# HLK-W806-KIT-V1_0.net
KiCad netlist of a schematic drawn in Altium Designer
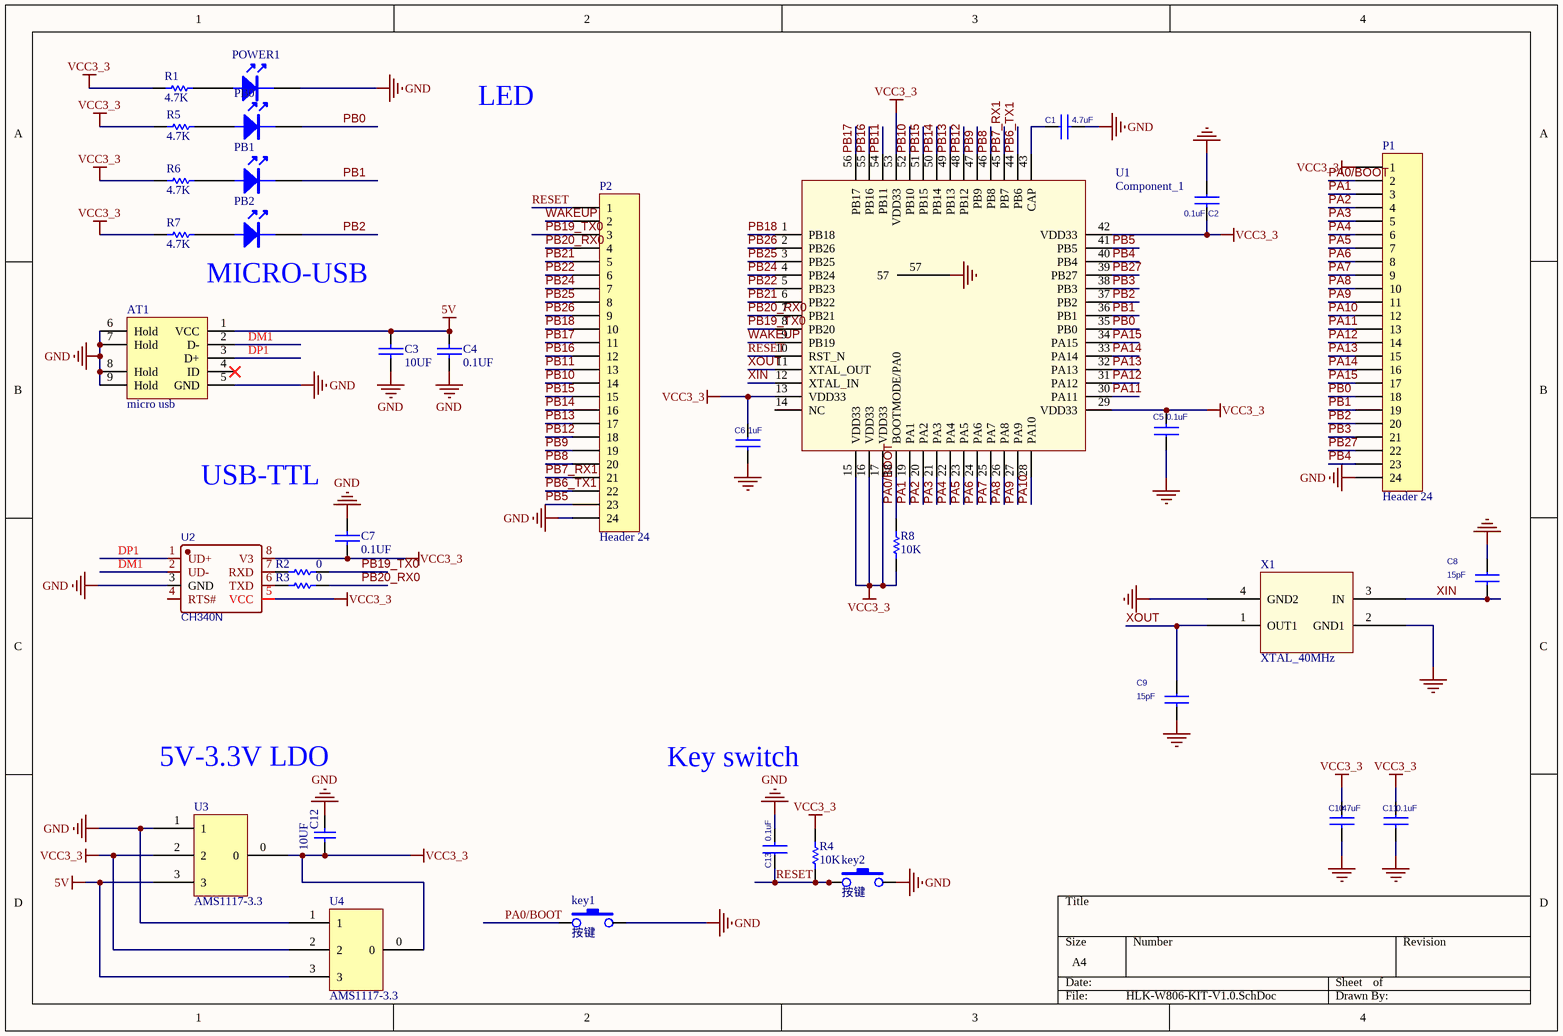
[diagram p0: HLK-W806-KIT-V1.0.SchDoc]

(export (version "E")
  (design (tool "Eeschema 10.0.6"))
  (components
    (comp (ref "AT1")
      (value "micro usb")
      (footprint "USB-MICRO_D")
      (libsource (lib "HLK-N10-KIT-V1.0") (part "USB-D"))
    )
    (comp (ref "C1") (value "4.7uF") (footprint "0603") (libsource (lib "*") (part "CAP NP_Dup1")))
    (comp (ref "C2") (value "0.1uF") (footprint "0603") (libsource (lib "*") (part "CAP NP_Dup1")))
    (comp (ref "C3")
      (value "10UF")
      (footprint "0603_1")
      (description "Capacitor")
      (libsource (lib "*") (part "CAP"))
    )
    (comp (ref "C4")
      (value "0.1UF")
      (footprint "0603_1")
      (description "Capacitor")
      (libsource (lib "*") (part "CAP"))
    )
    (comp (ref "C5") (value "0.1uF") (footprint "0603") (libsource (lib "*") (part "CAP NP_Dup1")))
    (comp (ref "C6") (value "1uF") (footprint "0603") (libsource (lib "*") (part "CAP NP_Dup1")))
    (comp (ref "C7")
      (value "0.1UF")
      (footprint "0603_1")
      (description "Capacitor")
      (libsource (lib "*") (part "CAP"))
    )
    (comp (ref "C8") (value "15pF") (footprint "0603") (libsource (lib "*") (part "CAP NP_Dup1")))
    (comp (ref "C9") (value "15pF") (footprint "0603") (libsource (lib "*") (part "CAP NP_Dup1")))
    (comp (ref "C10") (value "47uF") (footprint "R0805") (libsource (lib "*") (part "CAP NP_Dup1")))
    (comp (ref "C11") (value "0.1uF") (footprint "0603") (libsource (lib "*") (part "CAP NP_Dup1")))
    (comp (ref "C12")
      (value "10UF")
      (footprint "0603_1")
      (description "Capacitor")
      (fields (field (name "PUBLISHER") "Altium Limited"))
      (libsource (lib "Miscellaneous Devices") (part "Cap"))
    )
    (comp (ref "C13") (value "0.1uF") (footprint "0603") (libsource (lib "*") (part "CAP NP_Dup1")))
    (comp (ref "key1") (value "按键") (footprint "正按小龟") (libsource (lib "标准通用原理图库") (part "按键")))
    (comp (ref "key2") (value "按键") (footprint "正按小龟") (libsource (lib "标准通用原理图库") (part "按键")))
    (comp (ref "P1")
      (value "Header 24")
      (footprint "HDR1X24")
      (description "Header, 24-Pin")
      (fields (field (name "PUBLISHER") "Altium Limited"))
      (libsource (lib "Miscellaneous Connectors") (part "Header 24"))
    )
    (comp (ref "P2")
      (value "Header 24")
      (footprint "HDR1X24")
      (description "Header, 24-Pin")
      (fields (field (name "PUBLISHER") "Altium Limited"))
      (libsource (lib "Miscellaneous Connectors") (part "Header 24"))
    )
    (comp (ref "PB0")
      (value "~")
      (footprint "0603LED")
      (libsource (lib "Miscellaneous Devices") (part "LED"))
    )
    (comp (ref "PB1")
      (value "~")
      (footprint "0603LED")
      (libsource (lib "Miscellaneous Devices") (part "LED"))
    )
    (comp (ref "PB2")
      (value "~")
      (footprint "0603LED")
      (libsource (lib "Miscellaneous Devices") (part "LED"))
    )
    (comp (ref "POWER1")
      (value "~")
      (footprint "0603LED")
      (libsource (lib "Miscellaneous Devices") (part "LED"))
    )
    (comp (ref "R1")
      (value "4.7K")
      (footprint "0603_1")
      (description "Resistor")
      (fields (field (name "PUBLISHER") "Altium Limited"))
      (libsource (lib "Miscellaneous Devices") (part "Res1"))
    )
    (comp (ref "R2")
      (value "0")
      (footprint "0603_1")
      (description "Resistor")
      (fields (field (name "PUBLISHER") "Altium Limited"))
      (libsource (lib "Miscellaneous Devices") (part "Res1"))
    )
    (comp (ref "R3")
      (value "0")
      (footprint "0603_1")
      (description "Resistor")
      (fields (field (name "PUBLISHER") "Altium Limited"))
      (libsource (lib "Miscellaneous Devices") (part "Res1"))
    )
    (comp (ref "R4")
      (value "10K")
      (footprint "0603_1")
      (description "Resistor")
      (fields (field (name "PUBLISHER") "Altium Limited"))
      (libsource (lib "Miscellaneous Devices") (part "Res1"))
    )
    (comp (ref "R5")
      (value "4.7K")
      (footprint "0603_1")
      (description "Resistor")
      (fields (field (name "PUBLISHER") "Altium Limited"))
      (libsource (lib "Miscellaneous Devices") (part "Res1"))
    )
    (comp (ref "R6")
      (value "4.7K")
      (footprint "0603_1")
      (description "Resistor")
      (fields (field (name "PUBLISHER") "Altium Limited"))
      (libsource (lib "Miscellaneous Devices") (part "Res1"))
    )
    (comp (ref "R7")
      (value "4.7K")
      (footprint "0603_1")
      (description "Resistor")
      (fields (field (name "PUBLISHER") "Altium Limited"))
      (libsource (lib "Miscellaneous Devices") (part "Res1"))
    )
    (comp (ref "R8")
      (value "10K")
      (footprint "0603_1")
      (description "Resistor")
      (fields (field (name "PUBLISHER") "Altium Limited"))
      (libsource (lib "Miscellaneous Devices") (part "Res1"))
    )
    (comp (ref "U1")
      (value "Component_1")
      (footprint "LCC56 - duplicate1")
      (libsource (lib "Schlib") (part "Component_1"))
    )
    (comp (ref "U2")
      (value "CH340N")
      (footprint "SOP8")
      (fields (field (name "BOM_SUPPLIER PART") "C506813") (field (name "CONTRIBUTOR") "LCSC"))
      (libsource (lib "Schlib1") (part "CH340N"))
    )
    (comp (ref "U3")
      (value "AMS1117-3.3")
      (footprint "AMS1117")
      (libsource (lib "Schlib1") (part "Component_1"))
    )
    (comp (ref "U4")
      (value "AMS1117-3.3")
      (footprint "SOT223")
      (libsource (lib "Schlib1") (part "Component_1"))
    )
    (comp (ref "X1")
      (value "XTAL_40MHz")
      (footprint "SMD-3225")
      (libsource (lib "Schlib1") (part "XTAL_40MHz"))
    )
  )
  (nets
    (net (code "1") (name "/DM1") (class "Default")
      (node (ref "AT1") (pin "2") (pinfunction "D-_2") (pintype "passive"))
      (node (ref "U2") (pin "2") (pinfunction "UD-_2") (pintype "passive"))
    )
    (net (code "2") (name "/DP1") (class "Default")
      (node (ref "AT1") (pin "3") (pinfunction "D+_3") (pintype "passive"))
      (node (ref "U2") (pin "1") (pinfunction "UD+_1") (pintype "passive"))
    )
    (net (code "3") (name "/PA0{slash}BOOT") (class "Default")
      (node (ref "P1") (pin "2") (pinfunction "2_2") (pintype "passive"))
      (node (ref "R8") (pin "2") (pinfunction "2_2") (pintype "passive"))
      (node (ref "U1") (pin "18") (pinfunction "BOOTMODE/PA0_18") (pintype "passive"))
      (node (ref "key1") (pin "1") (pinfunction "1_1") (pintype "passive"))
    )
    (net (code "4") (name "/PA1") (class "Default")
      (node (ref "P1") (pin "3") (pinfunction "3_3") (pintype "passive"))
      (node (ref "U1") (pin "19") (pinfunction "PA1_19") (pintype "passive"))
    )
    (net (code "5") (name "/PA2") (class "Default")
      (node (ref "P1") (pin "4") (pinfunction "4_4") (pintype "passive"))
      (node (ref "U1") (pin "20") (pinfunction "PA2_20") (pintype "passive"))
    )
    (net (code "6") (name "/PA3") (class "Default")
      (node (ref "P1") (pin "5") (pinfunction "5_5") (pintype "passive"))
      (node (ref "U1") (pin "21") (pinfunction "PA3_21") (pintype "passive"))
    )
    (net (code "7") (name "/PA4") (class "Default")
      (node (ref "P1") (pin "6") (pinfunction "6_6") (pintype "passive"))
      (node (ref "U1") (pin "22") (pinfunction "PA4_22") (pintype "passive"))
    )
    (net (code "8") (name "/PA5") (class "Default")
      (node (ref "P1") (pin "7") (pinfunction "7_7") (pintype "passive"))
      (node (ref "U1") (pin "23") (pinfunction "PA5_23") (pintype "passive"))
    )
    (net (code "9") (name "/PA6") (class "Default")
      (node (ref "P1") (pin "8") (pinfunction "8_8") (pintype "passive"))
      (node (ref "U1") (pin "24") (pinfunction "PA6_24") (pintype "passive"))
    )
    (net (code "10") (name "/PA7") (class "Default")
      (node (ref "P1") (pin "9") (pinfunction "9_9") (pintype "passive"))
      (node (ref "U1") (pin "25") (pinfunction "PA7_25") (pintype "passive"))
    )
    (net (code "11") (name "/PA8") (class "Default")
      (node (ref "P1") (pin "10") (pinfunction "10_10") (pintype "passive"))
      (node (ref "U1") (pin "26") (pinfunction "PA8_26") (pintype "passive"))
    )
    (net (code "12") (name "/PA9") (class "Default")
      (node (ref "P1") (pin "11") (pinfunction "11_11") (pintype "passive"))
      (node (ref "U1") (pin "27") (pinfunction "PA9_27") (pintype "passive"))
    )
    (net (code "13") (name "/PA10") (class "Default")
      (node (ref "P1") (pin "12") (pinfunction "12_12") (pintype "passive"))
      (node (ref "U1") (pin "28") (pinfunction "PA10_28") (pintype "passive"))
    )
    (net (code "14") (name "/PA11") (class "Default")
      (node (ref "P1") (pin "13") (pinfunction "13_13") (pintype "passive"))
      (node (ref "U1") (pin "30") (pinfunction "PA11_30") (pintype "passive"))
    )
    (net (code "15") (name "/PA12") (class "Default")
      (node (ref "P1") (pin "14") (pinfunction "14_14") (pintype "passive"))
      (node (ref "U1") (pin "31") (pinfunction "PA12_31") (pintype "passive"))
    )
    (net (code "16") (name "/PA13") (class "Default")
      (node (ref "P1") (pin "15") (pinfunction "15_15") (pintype "passive"))
      (node (ref "U1") (pin "32") (pinfunction "PA13_32") (pintype "passive"))
    )
    (net (code "17") (name "/PA14") (class "Default")
      (node (ref "P1") (pin "16") (pinfunction "16_16") (pintype "passive"))
      (node (ref "U1") (pin "33") (pinfunction "PA14_33") (pintype "passive"))
    )
    (net (code "18") (name "/PA15") (class "Default")
      (node (ref "P1") (pin "17") (pinfunction "17_17") (pintype "passive"))
      (node (ref "U1") (pin "34") (pinfunction "PA15_34") (pintype "passive"))
    )
    (net (code "19") (name "/PB0") (class "Default")
      (node (ref "P1") (pin "18") (pinfunction "18_18") (pintype "passive"))
      (node (ref "PB0") (pin "2") (pinfunction "2_2") (pintype "passive"))
      (node (ref "U1") (pin "35") (pinfunction "PB0_35") (pintype "passive"))
    )
    (net (code "20") (name "/PB1") (class "Default")
      (node (ref "P1") (pin "19") (pinfunction "19_19") (pintype "passive"))
      (node (ref "PB1") (pin "2") (pinfunction "2_2") (pintype "passive"))
      (node (ref "U1") (pin "36") (pinfunction "PB1_36") (pintype "passive"))
    )
    (net (code "21") (name "/PB2") (class "Default")
      (node (ref "P1") (pin "20") (pinfunction "20_20") (pintype "passive"))
      (node (ref "PB2") (pin "2") (pinfunction "2_2") (pintype "passive"))
      (node (ref "U1") (pin "37") (pinfunction "PB2_37") (pintype "passive"))
    )
    (net (code "22") (name "/PB3") (class "Default")
      (node (ref "P1") (pin "21") (pinfunction "21_21") (pintype "passive"))
      (node (ref "U1") (pin "38") (pinfunction "PB3_38") (pintype "passive"))
    )
    (net (code "23") (name "/PB4") (class "Default")
      (node (ref "P1") (pin "23") (pinfunction "23_23") (pintype "passive"))
      (node (ref "U1") (pin "40") (pinfunction "PB4_40") (pintype "passive"))
    )
    (net (code "24") (name "/PB5") (class "Default")
      (node (ref "P2") (pin "23") (pinfunction "23_23") (pintype "passive"))
      (node (ref "U1") (pin "41") (pinfunction "PB5_41") (pintype "passive"))
    )
    (net (code "25") (name "/PB6_TX1") (class "Default")
      (node (ref "P2") (pin "22") (pinfunction "22_22") (pintype "passive"))
      (node (ref "U1") (pin "44") (pinfunction "PB6_44") (pintype "passive"))
    )
    (net (code "26") (name "/PB7_RX1") (class "Default")
      (node (ref "P2") (pin "21") (pinfunction "21_21") (pintype "passive"))
      (node (ref "U1") (pin "45") (pinfunction "PB7_45") (pintype "passive"))
    )
    (net (code "27") (name "/PB8") (class "Default")
      (node (ref "P2") (pin "20") (pinfunction "20_20") (pintype "passive"))
      (node (ref "U1") (pin "46") (pinfunction "PB8_46") (pintype "passive"))
    )
    (net (code "28") (name "/PB9") (class "Default")
      (node (ref "P2") (pin "19") (pinfunction "19_19") (pintype "passive"))
      (node (ref "U1") (pin "47") (pinfunction "PB9_47") (pintype "passive"))
    )
    (net (code "29") (name "/PB10") (class "Default")
      (node (ref "P2") (pin "14") (pinfunction "14_14") (pintype "passive"))
      (node (ref "U1") (pin "52") (pinfunction "PB10_52") (pintype "passive"))
    )
    (net (code "30") (name "/PB11") (class "Default")
      (node (ref "P2") (pin "13") (pinfunction "13_13") (pintype "passive"))
      (node (ref "U1") (pin "54") (pinfunction "PB11_54") (pintype "passive"))
    )
    (net (code "31") (name "/PB12") (class "Default")
      (node (ref "P2") (pin "18") (pinfunction "18_18") (pintype "passive"))
      (node (ref "U1") (pin "48") (pinfunction "PB12_48") (pintype "passive"))
    )
    (net (code "32") (name "/PB13") (class "Default")
      (node (ref "P2") (pin "17") (pinfunction "17_17") (pintype "passive"))
      (node (ref "U1") (pin "49") (pinfunction "PB13_49") (pintype "passive"))
    )
    (net (code "33") (name "/PB14") (class "Default")
      (node (ref "P2") (pin "16") (pinfunction "16_16") (pintype "passive"))
      (node (ref "U1") (pin "50") (pinfunction "PB14_50") (pintype "passive"))
    )
    (net (code "34") (name "/PB15") (class "Default")
      (node (ref "P2") (pin "15") (pinfunction "15_15") (pintype "passive"))
      (node (ref "U1") (pin "51") (pinfunction "PB15_51") (pintype "passive"))
    )
    (net (code "35") (name "/PB16") (class "Default")
      (node (ref "P2") (pin "12") (pinfunction "12_12") (pintype "passive"))
      (node (ref "U1") (pin "55") (pinfunction "PB16_55") (pintype "passive"))
    )
    (net (code "36") (name "/PB17") (class "Default")
      (node (ref "P2") (pin "11") (pinfunction "11_11") (pintype "passive"))
      (node (ref "U1") (pin "56") (pinfunction "PB17_56") (pintype "passive"))
    )
    (net (code "37") (name "/PB18") (class "Default")
      (node (ref "P2") (pin "10") (pinfunction "10_10") (pintype "passive"))
      (node (ref "U1") (pin "1") (pinfunction "PB18_1") (pintype "passive"))
    )
    (net (code "38") (name "/PB19_TX0") (class "Default")
      (node (ref "P2") (pin "3") (pinfunction "3_3") (pintype "passive"))
      (node (ref "R2") (pin "2") (pinfunction "2_2") (pintype "passive"))
      (node (ref "U1") (pin "8") (pinfunction "PB20_8") (pintype "passive"))
    )
    (net (code "39") (name "/PB20_RX0") (class "Default")
      (node (ref "P2") (pin "4") (pinfunction "4_4") (pintype "passive"))
      (node (ref "R3") (pin "2") (pinfunction "2_2") (pintype "passive"))
      (node (ref "U1") (pin "7") (pinfunction "PB21_7") (pintype "passive"))
    )
    (net (code "40") (name "/PB21") (class "Default")
      (node (ref "P2") (pin "5") (pinfunction "5_5") (pintype "passive"))
      (node (ref "U1") (pin "6") (pinfunction "PB22_6") (pintype "passive"))
    )
    (net (code "41") (name "/PB22") (class "Default")
      (node (ref "P2") (pin "6") (pinfunction "6_6") (pintype "passive"))
      (node (ref "U1") (pin "5") (pinfunction "PB23_5") (pintype "passive"))
    )
    (net (code "42") (name "/PB24") (class "Default")
      (node (ref "P2") (pin "7") (pinfunction "7_7") (pintype "passive"))
      (node (ref "U1") (pin "4") (pinfunction "PB24_4") (pintype "passive"))
    )
    (net (code "43") (name "/PB25") (class "Default")
      (node (ref "P2") (pin "8") (pinfunction "8_8") (pintype "passive"))
      (node (ref "U1") (pin "3") (pinfunction "PB25_3") (pintype "passive"))
    )
    (net (code "44") (name "/PB26") (class "Default")
      (node (ref "P2") (pin "9") (pinfunction "9_9") (pintype "passive"))
      (node (ref "U1") (pin "2") (pinfunction "PB26_2") (pintype "passive"))
    )
    (net (code "45") (name "/PB27") (class "Default")
      (node (ref "P1") (pin "22") (pinfunction "22_22") (pintype "passive"))
      (node (ref "U1") (pin "39") (pinfunction "PB27_39") (pintype "passive"))
    )
    (net (code "46") (name "/RESET") (class "Default")
      (node (ref "C13") (pin "1") (pinfunction "1_1") (pintype "passive"))
      (node (ref "P2") (pin "1") (pinfunction "1_1") (pintype "passive"))
      (node (ref "R4") (pin "1") (pinfunction "1_1") (pintype "passive"))
      (node (ref "U1") (pin "10") (pinfunction "RST_N_10") (pintype "passive"))
      (node (ref "key2") (pin "1") (pinfunction "1_1") (pintype "passive"))
    )
    (net (code "47") (name "/WAKEUP") (class "Default")
      (node (ref "P2") (pin "2") (pinfunction "2_2") (pintype "passive"))
      (node (ref "U1") (pin "9") (pinfunction "PB19_9") (pintype "passive"))
    )
    (net (code "48") (name "/XIN") (class "Default")
      (node (ref "C8") (pin "2") (pinfunction "2_2") (pintype "passive"))
      (node (ref "U1") (pin "12") (pinfunction "XTAL_IN_12") (pintype "passive"))
      (node (ref "X1") (pin "3") (pinfunction "IN_3") (pintype "passive"))
    )
    (net (code "49") (name "/XOUT") (class "Default")
      (node (ref "C9") (pin "1") (pinfunction "1_1") (pintype "passive"))
      (node (ref "U1") (pin "11") (pinfunction "XTAL_OUT_11") (pintype "passive"))
      (node (ref "X1") (pin "1") (pinfunction "OUT1_1") (pintype "passive"))
    )
    (net (code "50") (name "5V") (class "Default")
      (node (ref "AT1") (pin "1") (pinfunction "VCC_1") (pintype "passive"))
      (node (ref "C3") (pin "2") (pinfunction "2_2") (pintype "passive"))
      (node (ref "C4") (pin "2") (pinfunction "2_2") (pintype "passive"))
      (node (ref "U3") (pin "3") (pinfunction "3_3") (pintype "passive"))
      (node (ref "U4") (pin "3") (pinfunction "3_3") (pintype "passive"))
    )
    (net (code "51") (name "GND") (class "Default")
      (node (ref "AT1") (pin "5") (pinfunction "GND_5") (pintype "passive"))
      (node (ref "AT1") (pin "6") (pinfunction "Hold_6") (pintype "passive"))
      (node (ref "AT1") (pin "7") (pinfunction "Hold_7") (pintype "passive"))
      (node (ref "AT1") (pin "8") (pinfunction "Hold_8") (pintype "passive"))
      (node (ref "AT1") (pin "9") (pinfunction "Hold_9") (pintype "passive"))
      (node (ref "C1") (pin "2") (pinfunction "2_2") (pintype "passive"))
      (node (ref "C10") (pin "2") (pinfunction "2_2") (pintype "passive"))
      (node (ref "C11") (pin "2") (pinfunction "2_2") (pintype "passive"))
      (node (ref "C12") (pin "1") (pinfunction "1_1") (pintype "passive"))
      (node (ref "C13") (pin "2") (pinfunction "2_2") (pintype "passive"))
      (node (ref "C2") (pin "1") (pinfunction "1_1") (pintype "passive"))
      (node (ref "C3") (pin "1") (pinfunction "1_1") (pintype "passive"))
      (node (ref "C4") (pin "1") (pinfunction "1_1") (pintype "passive"))
      (node (ref "C5") (pin "1") (pinfunction "1_1") (pintype "passive"))
      (node (ref "C6") (pin "2") (pinfunction "2_2") (pintype "passive"))
      (node (ref "C7") (pin "1") (pinfunction "1_1") (pintype "passive"))
      (node (ref "C8") (pin "1") (pinfunction "1_1") (pintype "passive"))
      (node (ref "C9") (pin "2") (pinfunction "2_2") (pintype "passive"))
      (node (ref "P1") (pin "24") (pinfunction "24_24") (pintype "passive"))
      (node (ref "P2") (pin "24") (pinfunction "24_24") (pintype "passive"))
      (node (ref "POWER1") (pin "2") (pinfunction "2_2") (pintype "passive"))
      (node (ref "U1") (pin "57") (pinfunction "57_57") (pintype "passive"))
      (node (ref "U2") (pin "3") (pinfunction "GND_3") (pintype "passive"))
      (node (ref "U3") (pin "1") (pinfunction "1_1") (pintype "passive"))
      (node (ref "U4") (pin "1") (pinfunction "1_1") (pintype "passive"))
      (node (ref "X1") (pin "2") (pinfunction "GND1_2") (pintype "passive"))
      (node (ref "X1") (pin "4") (pinfunction "GND2_4") (pintype "passive"))
      (node (ref "key1") (pin "2") (pinfunction "2_2") (pintype "passive"))
      (node (ref "key2") (pin "2") (pinfunction "2_2") (pintype "passive"))
    )
    (net (code "52") (name "Net-(PB0-Pad1)") (class "Default")
      (node (ref "PB0") (pin "1") (pinfunction "1_1") (pintype "passive"))
      (node (ref "R5") (pin "2") (pinfunction "2_2") (pintype "passive"))
    )
    (net (code "53") (name "Net-(PB1-Pad1)") (class "Default")
      (node (ref "PB1") (pin "1") (pinfunction "1_1") (pintype "passive"))
      (node (ref "R6") (pin "2") (pinfunction "2_2") (pintype "passive"))
    )
    (net (code "54") (name "Net-(PB2-Pad1)") (class "Default")
      (node (ref "PB2") (pin "1") (pinfunction "1_1") (pintype "passive"))
      (node (ref "R7") (pin "2") (pinfunction "2_2") (pintype "passive"))
    )
    (net (code "55") (name "Net-(POWER1-Pad1)") (class "Default")
      (node (ref "POWER1") (pin "1") (pinfunction "1_1") (pintype "passive"))
      (node (ref "R1") (pin "2") (pinfunction "2_2") (pintype "passive"))
    )
    (net (code "56") (name "Net-(U1-CAP)") (class "Default")
      (node (ref "C1") (pin "1") (pinfunction "1_1") (pintype "passive"))
      (node (ref "U1") (pin "43") (pinfunction "CAP_43") (pintype "passive"))
    )
    (net (code "57") (name "Net-(U2-RXD)") (class "Default")
      (node (ref "R2") (pin "1") (pinfunction "1_1") (pintype "passive"))
      (node (ref "U2") (pin "7") (pinfunction "RXD_7") (pintype "passive"))
    )
    (net (code "58") (name "Net-(U2-TXD)") (class "Default")
      (node (ref "R3") (pin "1") (pinfunction "1_1") (pintype "passive"))
      (node (ref "U2") (pin "6") (pinfunction "TXD_6") (pintype "passive"))
    )
    (net (code "59") (name "VCC3_3") (class "Default")
      (node (ref "C10") (pin "1") (pinfunction "1_1") (pintype "passive"))
      (node (ref "C11") (pin "1") (pinfunction "1_1") (pintype "passive"))
      (node (ref "C12") (pin "2") (pinfunction "2_2") (pintype "passive"))
      (node (ref "C2") (pin "2") (pinfunction "2_2") (pintype "passive"))
      (node (ref "C5") (pin "2") (pinfunction "2_2") (pintype "passive"))
      (node (ref "C6") (pin "1") (pinfunction "1_1") (pintype "passive"))
      (node (ref "C7") (pin "2") (pinfunction "2_2") (pintype "passive"))
      (node (ref "P1") (pin "1") (pinfunction "1_1") (pintype "passive"))
      (node (ref "R1") (pin "1") (pinfunction "1_1") (pintype "passive"))
      (node (ref "R4") (pin "2") (pinfunction "2_2") (pintype "passive"))
      (node (ref "R5") (pin "1") (pinfunction "1_1") (pintype "passive"))
      (node (ref "R6") (pin "1") (pinfunction "1_1") (pintype "passive"))
      (node (ref "R7") (pin "1") (pinfunction "1_1") (pintype "passive"))
      (node (ref "R8") (pin "1") (pinfunction "1_1") (pintype "passive"))
      (node (ref "U1") (pin "13") (pinfunction "VDD33_13") (pintype "passive"))
      (node (ref "U1") (pin "15") (pinfunction "VDD33_15") (pintype "passive"))
      (node (ref "U1") (pin "16") (pinfunction "VDD33_16") (pintype "passive"))
      (node (ref "U1") (pin "17") (pinfunction "VDD33_17") (pintype "passive"))
      (node (ref "U1") (pin "29") (pinfunction "VDD33_29") (pintype "passive"))
      (node (ref "U1") (pin "42") (pinfunction "VDD33_42") (pintype "passive"))
      (node (ref "U1") (pin "53") (pinfunction "VDD33_53") (pintype "passive"))
      (node (ref "U2") (pin "5") (pinfunction "VCC_5") (pintype "passive"))
      (node (ref "U2") (pin "8") (pinfunction "V3_8") (pintype "passive"))
      (node (ref "U3") (pin "0") (pinfunction "0_0") (pintype "passive"))
      (node (ref "U3") (pin "2") (pinfunction "2_2") (pintype "passive"))
      (node (ref "U4") (pin "0") (pinfunction "0_0") (pintype "passive"))
      (node (ref "U4") (pin "2") (pinfunction "2_2") (pintype "passive"))
    )
    (net (code "60") (name "unconnected-(AT1-ID-Pad4)") (class "Default")
      (node (ref "AT1") (pin "4") (pinfunction "ID_4") (pintype "passive+no_connect"))
    )
    (net (code "61") (name "unconnected-(U1-NC-Pad14)") (class "Default")
      (node (ref "U1") (pin "14") (pinfunction "NC_14") (pintype "passive"))
    )
    (net (code "62") (name "unconnected-(U2-RTS#-Pad4)") (class "Default")
      (node (ref "U2") (pin "4") (pinfunction "RTS#_4") (pintype "passive"))
    )
  )
)
